# OreSat0_plusZendcard.net
KiCad netlist of a schematic drawn in EAGLE
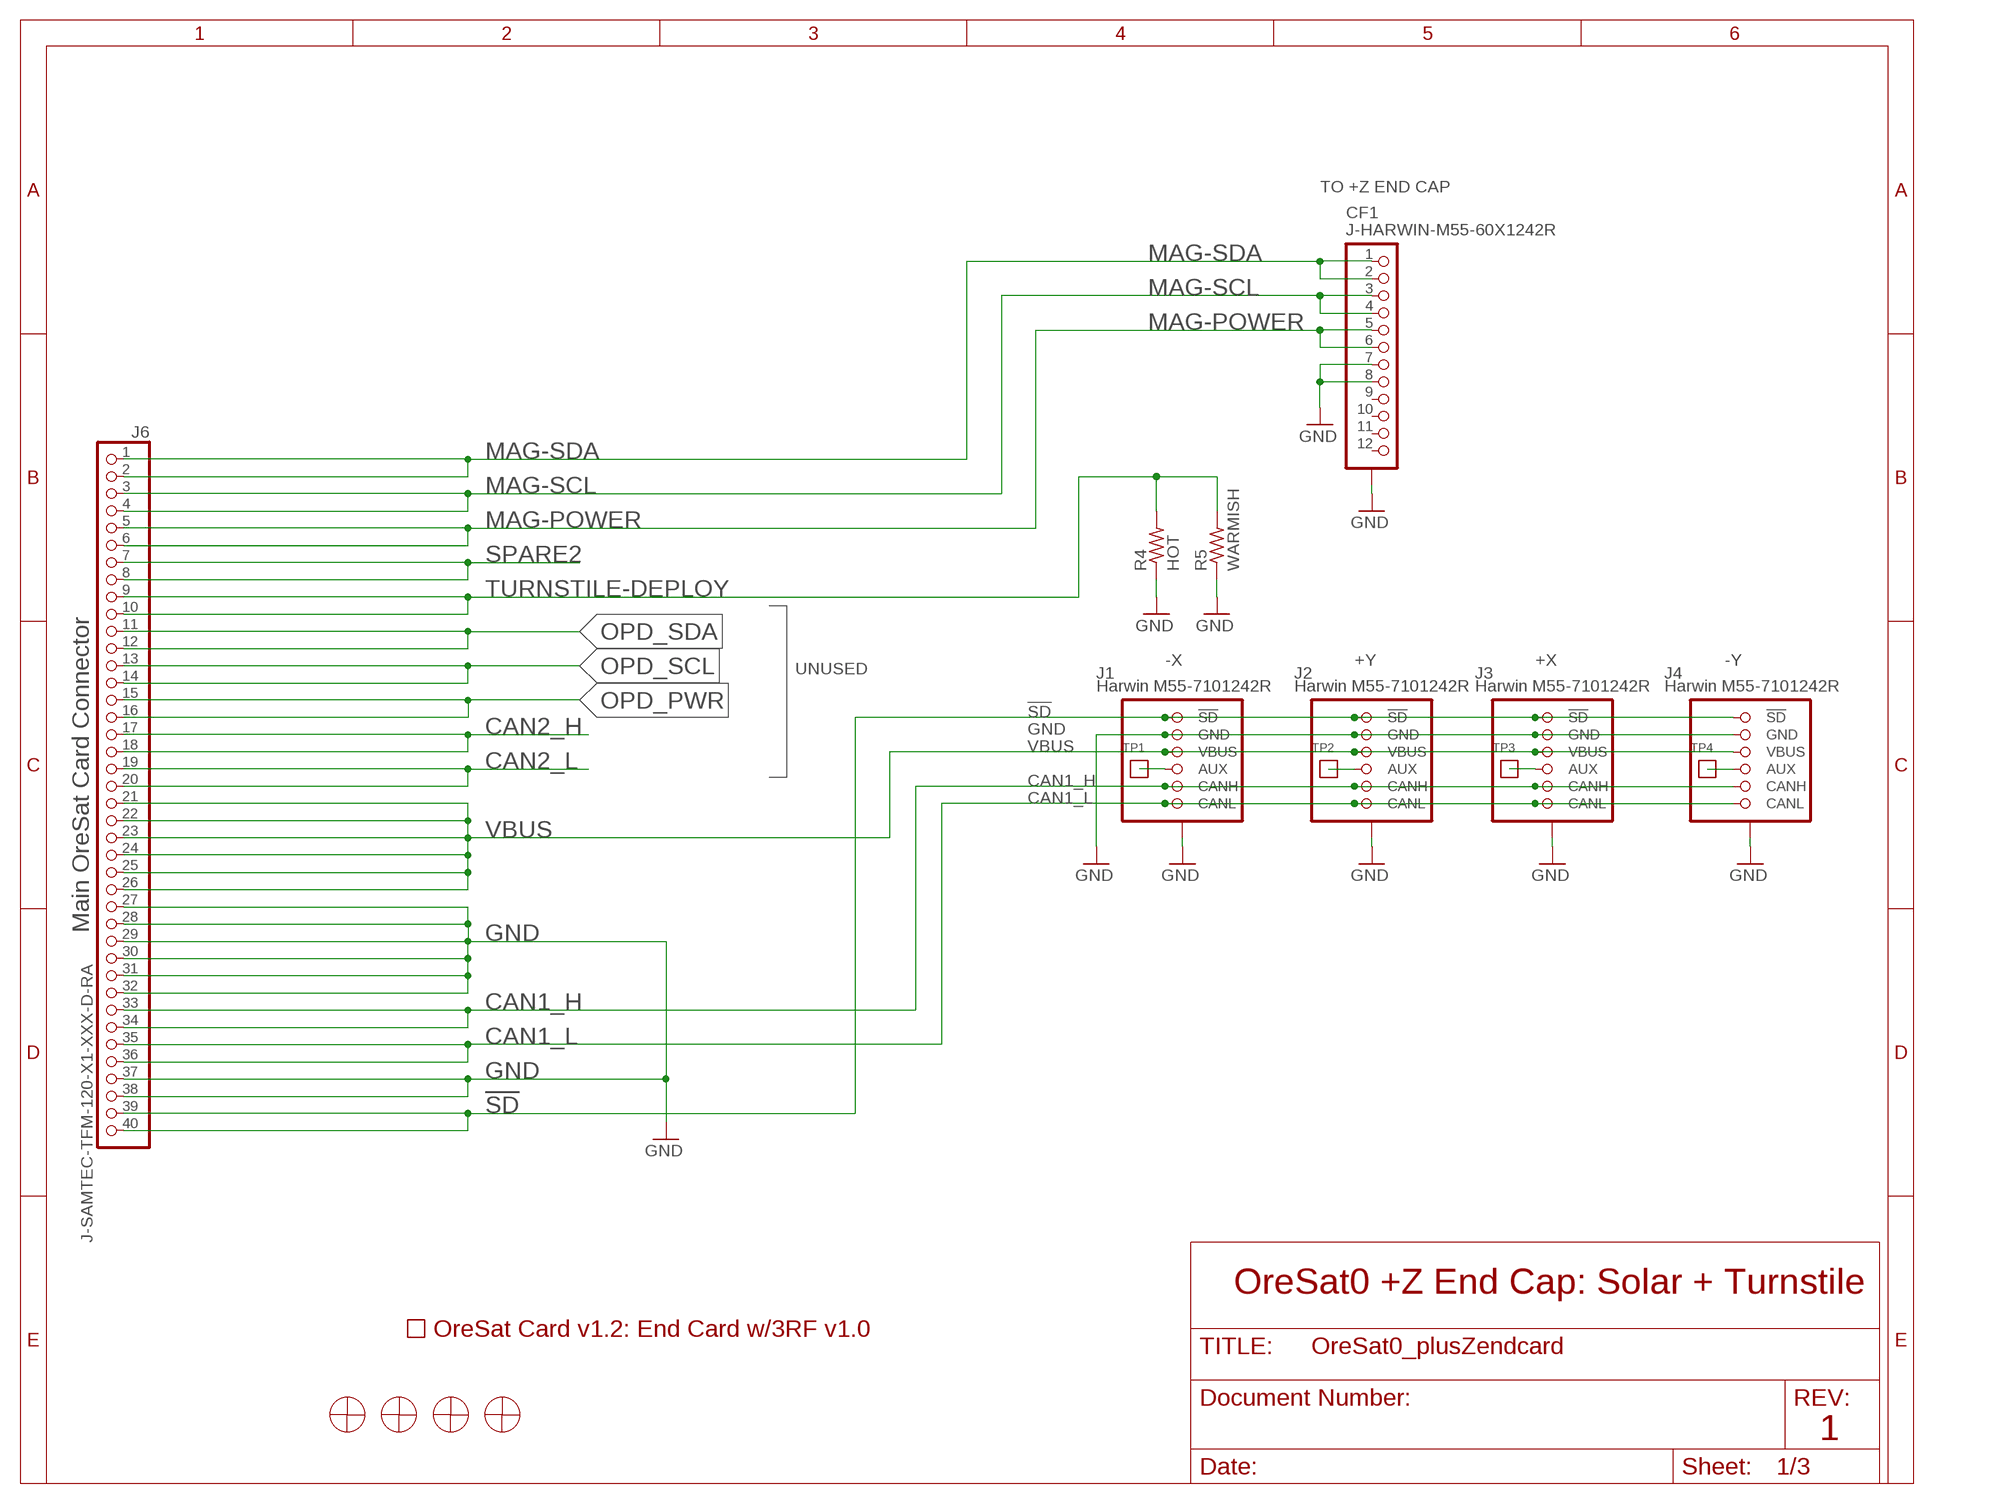
[diagram p0: schematic, sheet 1]
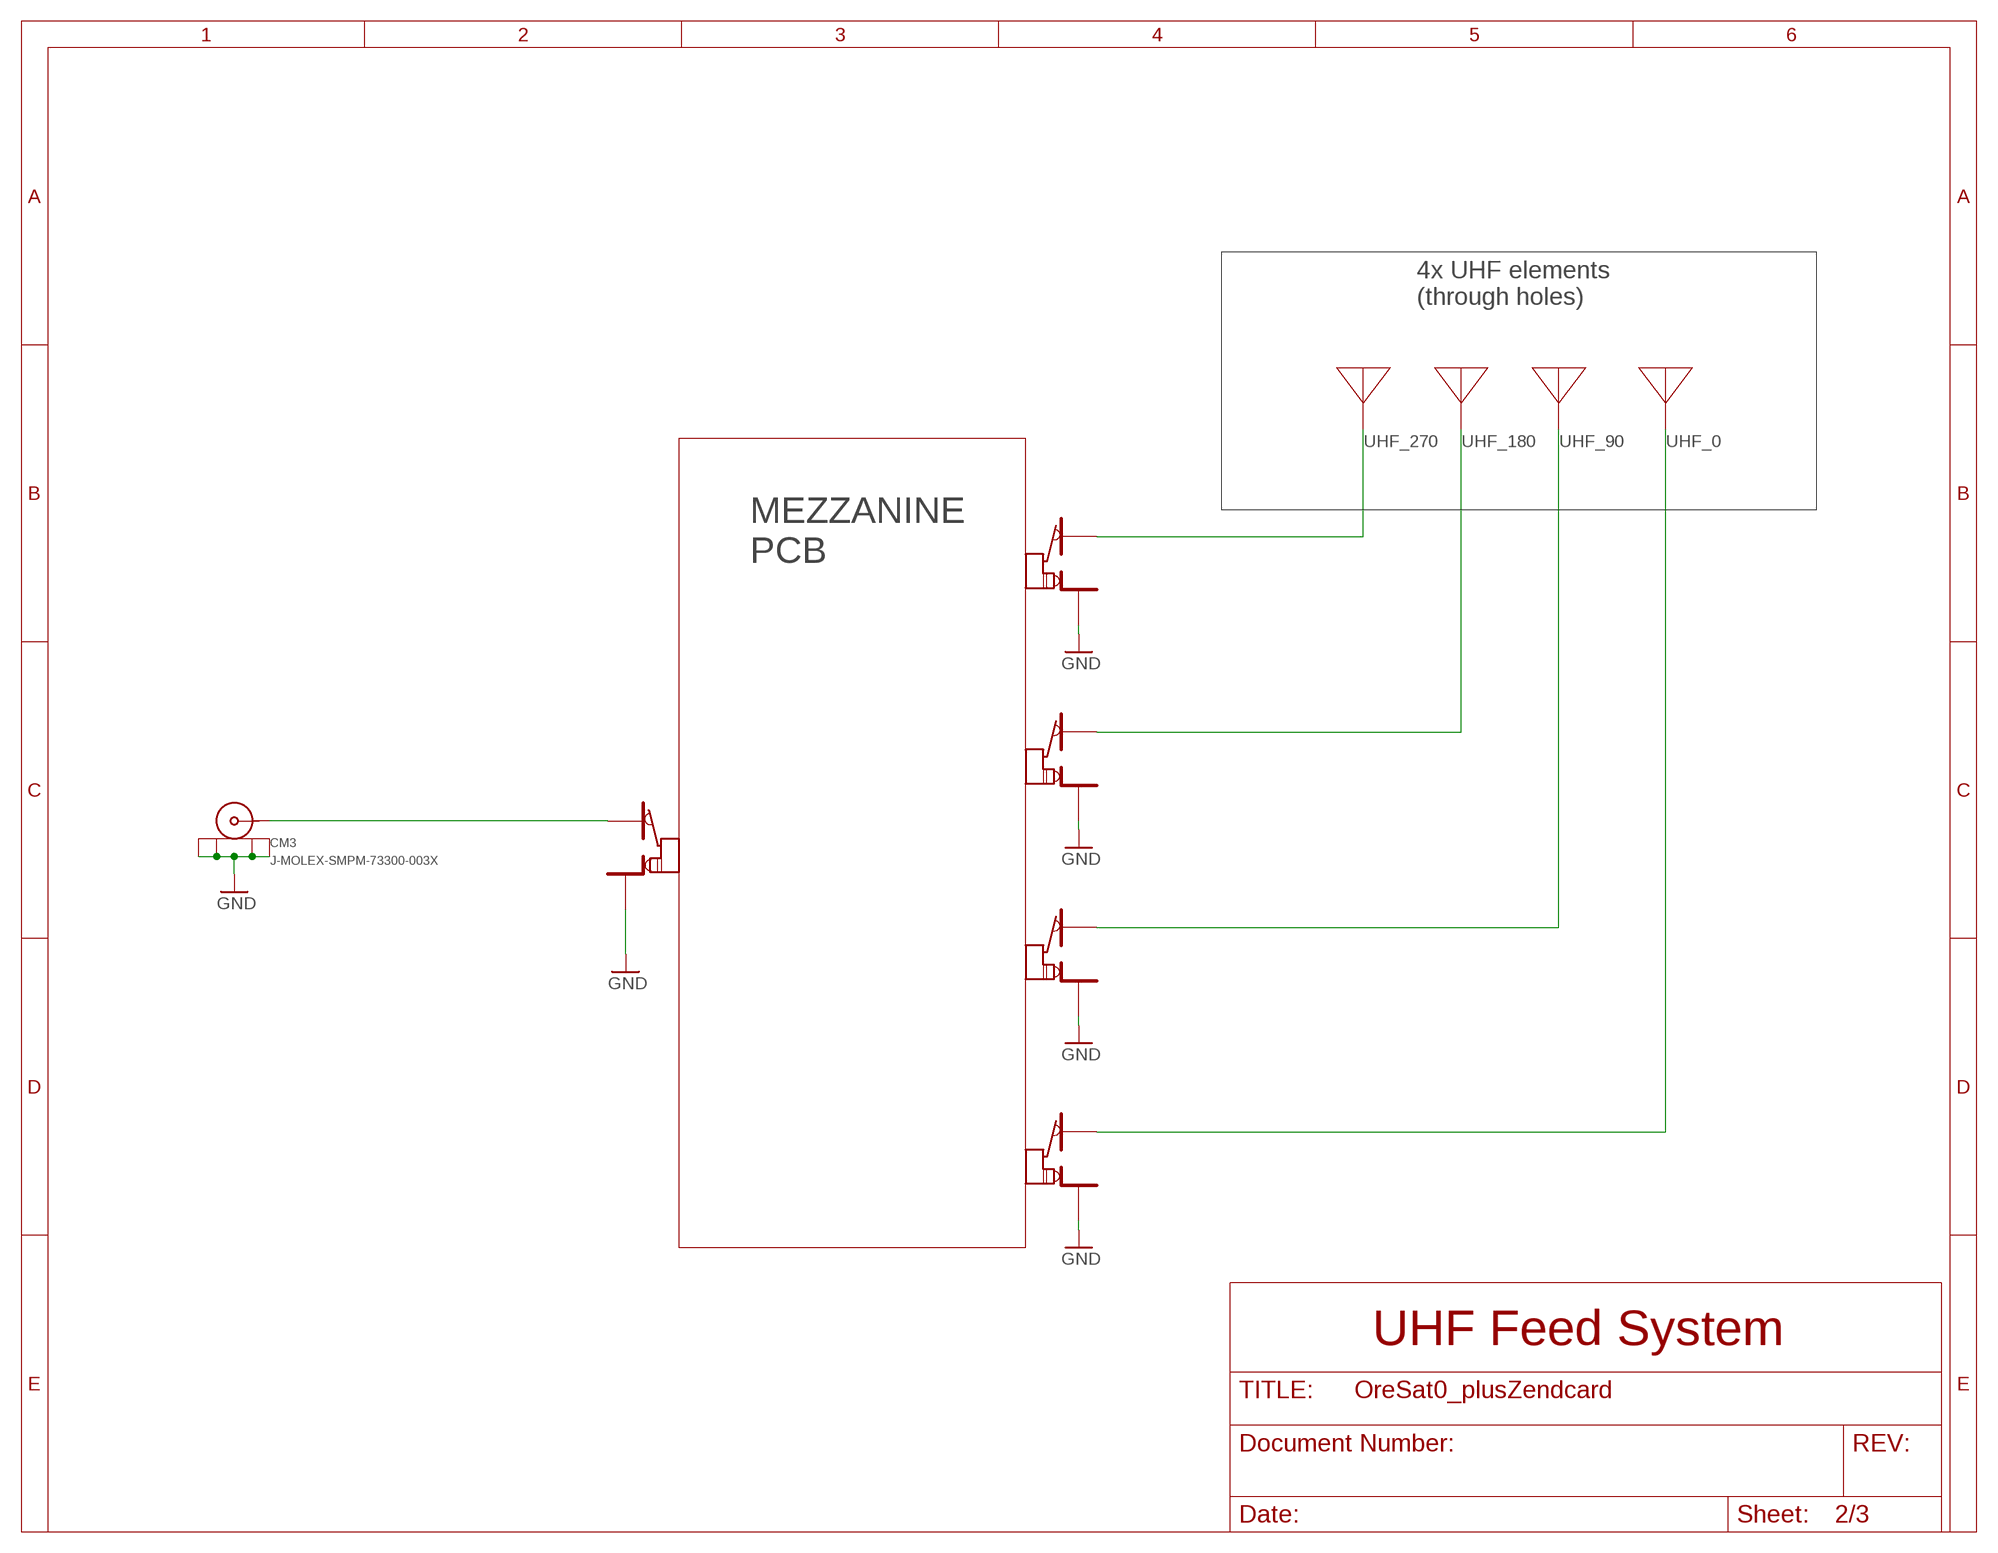
[diagram p1: schematic, sheet 2]
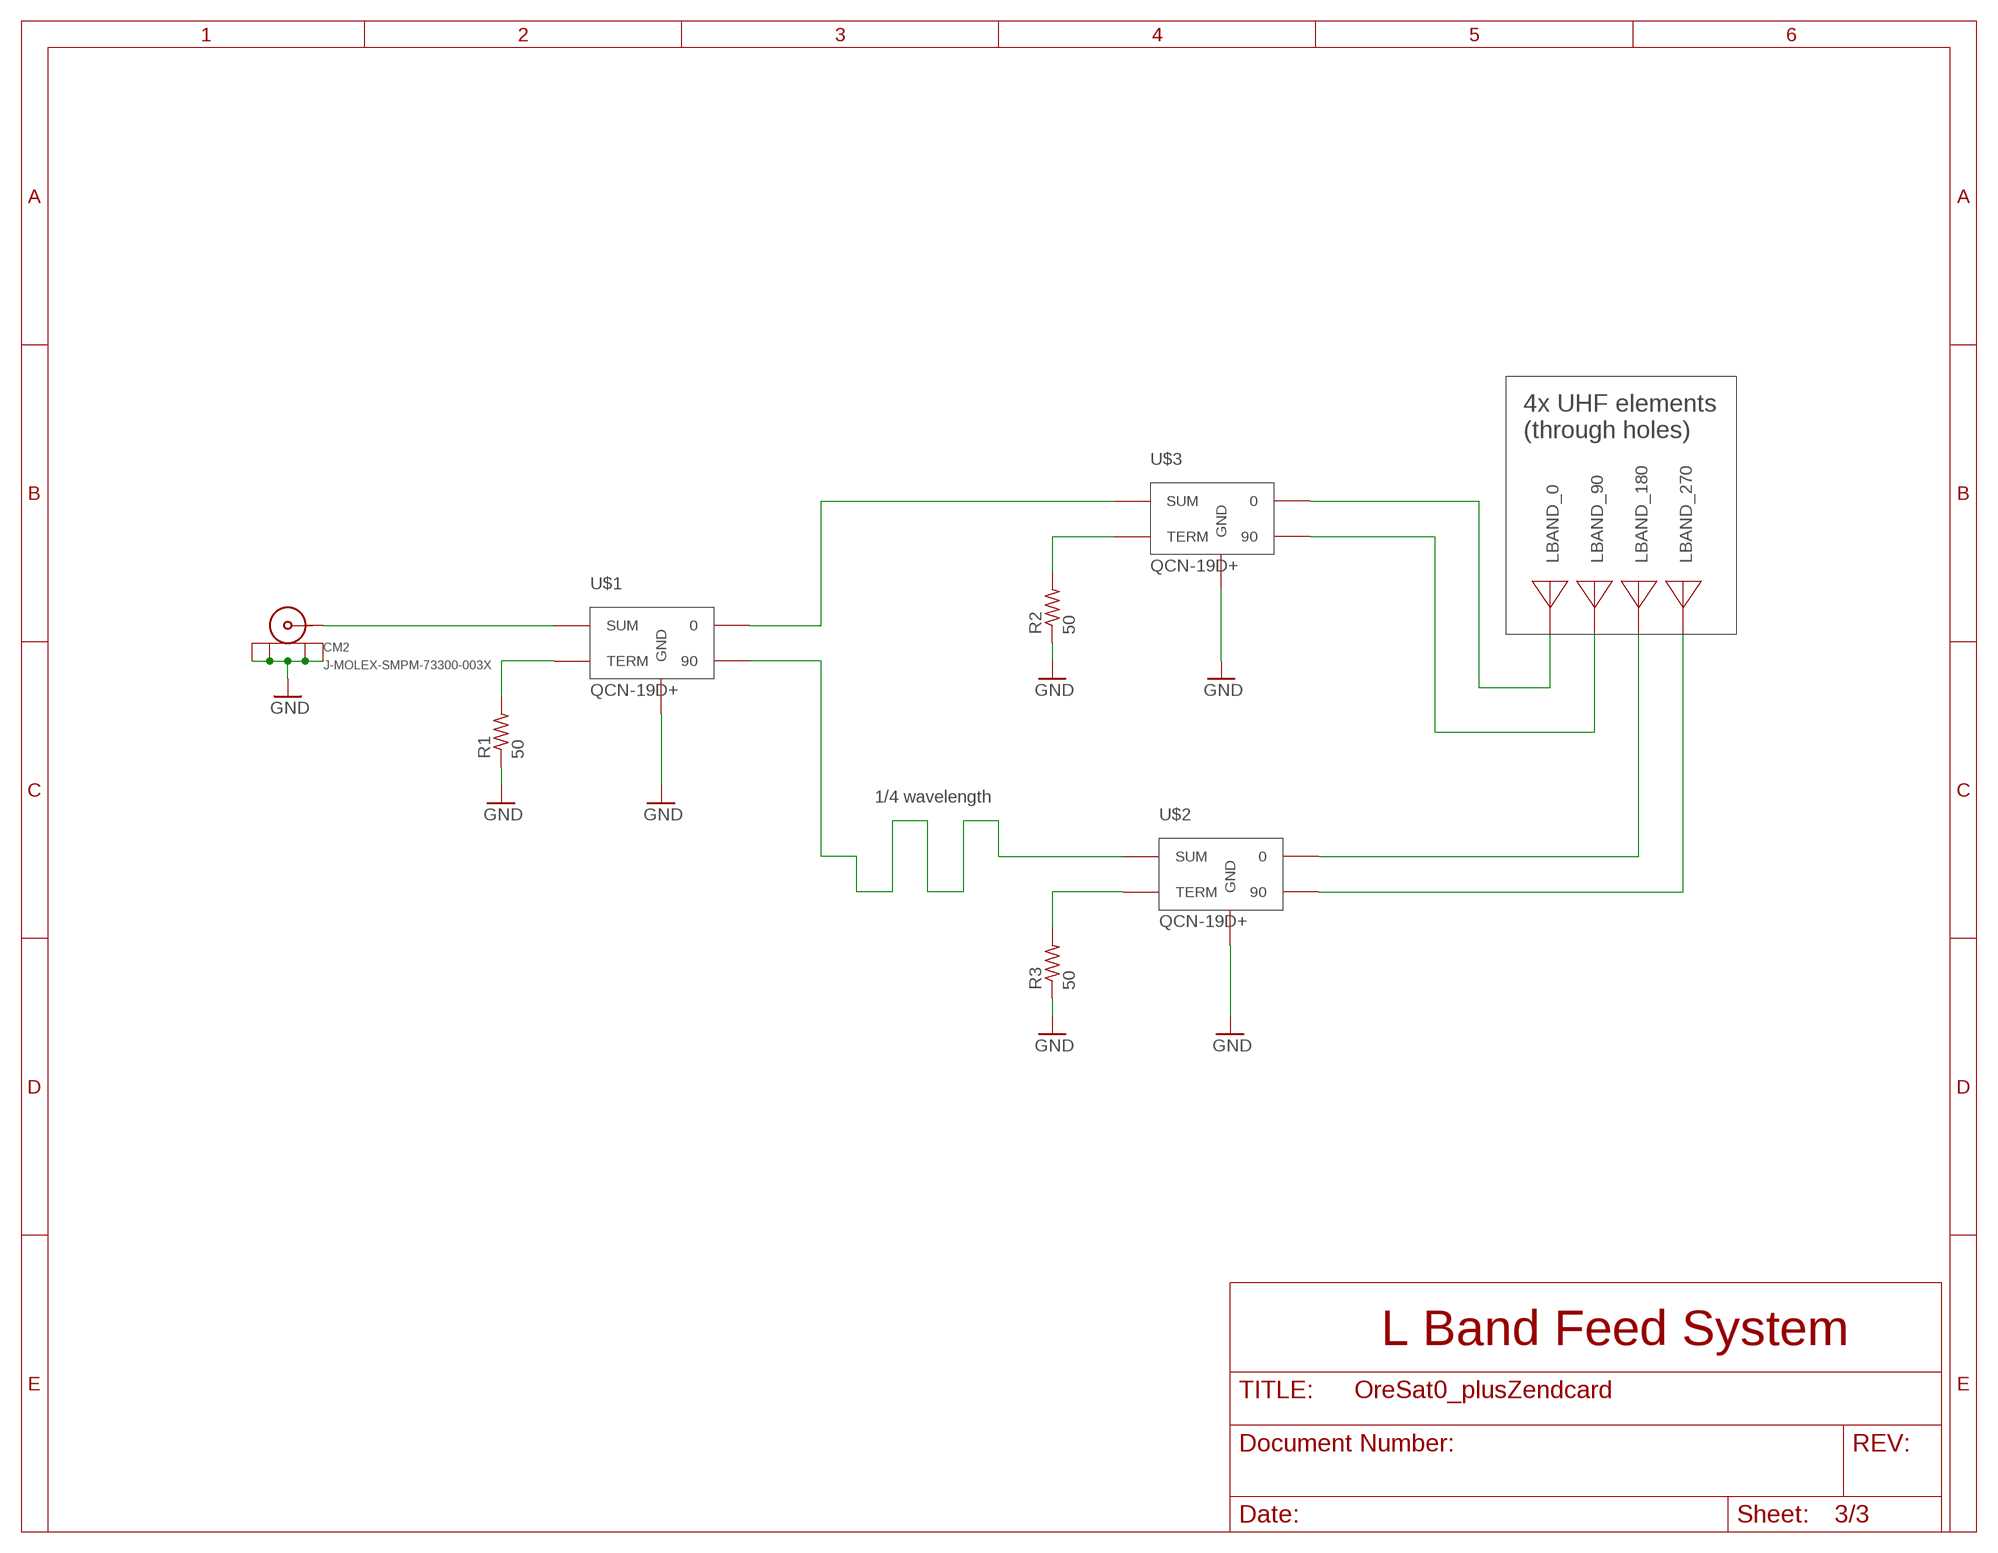
[diagram p2: schematic, sheet 3]

(export (version "E")
  (design (tool "Eeschema 10.0.6"))
  (components
    (comp (ref "CM2")
      (value "J-MOLEX-SMPM-73300-003X")
      (footprint "eagle-import:J-MOLEX-SMPM-73300-003X")
      (fields (field (name "MFG") "MOLEX"))
      (libsource (lib "eagle-import") (part "J-MOLEX-SMPM-73300-003X"))
    )
    (comp (ref "R1")
      (value "50")
      (footprint "eagle-import:.0805-B-NOSILK")
      (libsource (lib "eagle-import") (part "R-US_0805-B-NOSILK"))
    )
    (comp (ref "R2")
      (value "50")
      (footprint "eagle-import:.0805-B-NOSILK")
      (libsource (lib "eagle-import") (part "R-US_0805-B-NOSILK"))
    )
    (comp (ref "R3")
      (value "50")
      (footprint "eagle-import:.0805-B-NOSILK")
      (libsource (lib "eagle-import") (part "R-US_0805-B-NOSILK"))
    )
    (comp (ref "U$1")
      (value "QCN-19D+")
      (footprint "eagle-import:QVN-19D+")
      (libsource (lib "eagle-import") (part "QCN-19D+"))
    )
    (comp (ref "U$2")
      (value "QCN-19D+")
      (footprint "eagle-import:QVN-19D+")
      (libsource (lib "eagle-import") (part "QCN-19D+"))
    )
    (comp (ref "U$3")
      (value "QCN-19D+")
      (footprint "eagle-import:QVN-19D+")
      (libsource (lib "eagle-import") (part "QCN-19D+"))
    )
    (comp (ref "CM3")
      (value "J-MOLEX-SMPM-73300-003X")
      (footprint "eagle-import:J-MOLEX-SMPM-73300-003X")
      (fields (field (name "MFG") "MOLEX"))
      (libsource (lib "eagle-import") (part "J-MOLEX-SMPM-73300-003X"))
    )
    (comp (ref "U$4")
      (value "R107064070_CONTACT")
      (footprint "eagle-import:R107064070_CONTACT")
      (libsource (lib "eagle-import") (part "R107064070_CONTACT"))
    )
    (comp (ref "U$5")
      (value "R107064070_CONTACT")
      (footprint "eagle-import:R107064070_CONTACT")
      (libsource (lib "eagle-import") (part "R107064070_CONTACT"))
    )
    (comp (ref "U$6")
      (value "R107064070_CONTACT")
      (footprint "eagle-import:R107064070_CONTACT")
      (libsource (lib "eagle-import") (part "R107064070_CONTACT"))
    )
    (comp (ref "U$7")
      (value "R107064070_CONTACT")
      (footprint "eagle-import:R107064070_CONTACT")
      (libsource (lib "eagle-import") (part "R107064070_CONTACT"))
    )
    (comp (ref "U$8")
      (value "R107064070_CONTACT")
      (footprint "eagle-import:R107064070_CONTACT")
      (libsource (lib "eagle-import") (part "R107064070_CONTACT"))
    )
    (comp (ref "CF1")
      (value "J-HARWIN-M55-60X1242R")
      (footprint "eagle-import:HARWIN-M55-60X1242R")
      (fields (field (name "MFG") "Harwin"))
      (libsource (lib "eagle-import") (part "J-HARWIN-M55-60X1242R"))
    )
    (comp (ref "J1")
      (value "Harwin M55-7101242R")
      (footprint "eagle-import:M55-7101242R")
      (fields (field (name "MFG") "Harwin Inc."))
      (libsource (lib "eagle-import") (part "SOLAR-CARD-CONNECTOR"))
    )
    (comp (ref "J2")
      (value "Harwin M55-7101242R")
      (footprint "eagle-import:M55-7101242R")
      (fields (field (name "MFG") "Harwin Inc."))
      (libsource (lib "eagle-import") (part "SOLAR-CARD-CONNECTOR"))
    )
    (comp (ref "J3")
      (value "Harwin M55-7101242R")
      (footprint "eagle-import:M55-7101242R")
      (fields (field (name "MFG") "Harwin Inc."))
      (libsource (lib "eagle-import") (part "SOLAR-CARD-CONNECTOR"))
    )
    (comp (ref "J4")
      (value "Harwin M55-7101242R")
      (footprint "eagle-import:M55-7101242R")
      (fields (field (name "MFG") "Harwin Inc."))
      (libsource (lib "eagle-import") (part "SOLAR-CARD-CONNECTOR"))
    )
    (comp (ref "J6")
      (value "J-SAMTEC-TFM-120-X1-XXX-D-RA")
      (footprint "eagle-import:J-SAMTEC-TFM-120-X1-XXX-D-RA")
      (fields (field (name "MFR") "Samtec") (field (name "MPN") "TFM-120-01-L-D-RA"))
      (libsource (lib "eagle-import") (part "J-SAMTEC-TFM-120-X1-XXX-D-RA"))
    )
    (comp (ref "PCB1")
      (value "ORESAT-CARD-V1.3-END-CARD-3RF-V1.0")
      (footprint "eagle-import:ORESAT-CARD-V1.3-END-CARD-3RF-V1.0")
      (libsource (lib "eagle-import") (part "ORESAT-CARD-V1.3-END-CARD-3RF-V1.0"))
    )
    (comp (ref "R4")
      (value "HOT")
      (footprint "eagle-import:0309_12")
      (libsource (lib "eagle-import") (part "R-US_0309/12"))
    )
    (comp (ref "R5")
      (value "WARMISH")
      (footprint "eagle-import:0309_12")
      (libsource (lib "eagle-import") (part "R-US_0309/12"))
    )
    (comp (ref "TP1")
      (value "TEST-POINT-LARGE-SQUARE")
      (footprint "eagle-import:1X01")
      (libsource (lib "eagle-import") (part "TEST-POINT-LARGE-SQUARE"))
    )
    (comp (ref "TP2")
      (value "TEST-POINT-LARGE-SQUARE")
      (footprint "eagle-import:1X01")
      (libsource (lib "eagle-import") (part "TEST-POINT-LARGE-SQUARE"))
    )
    (comp (ref "TP3")
      (value "TEST-POINT-LARGE-SQUARE")
      (footprint "eagle-import:1X01")
      (libsource (lib "eagle-import") (part "TEST-POINT-LARGE-SQUARE"))
    )
    (comp (ref "TP4")
      (value "TEST-POINT-LARGE-SQUARE")
      (footprint "eagle-import:1X01")
      (libsource (lib "eagle-import") (part "TEST-POINT-LARGE-SQUARE"))
    )
    (comp (ref "U$9")
      (value "MCMASTER-94100A150")
      (footprint "eagle-import:MCMASTER-94100A150")
      (libsource (lib "eagle-import") (part "MCMASTER-94100A150"))
    )
    (comp (ref "U$10")
      (value "MCMASTER-94100A150")
      (footprint "eagle-import:MCMASTER-94100A150")
      (libsource (lib "eagle-import") (part "MCMASTER-94100A150"))
    )
    (comp (ref "U$11")
      (value "MCMASTER-94100A150")
      (footprint "eagle-import:MCMASTER-94100A150")
      (libsource (lib "eagle-import") (part "MCMASTER-94100A150"))
    )
    (comp (ref "U$12")
      (value "MCMASTER-94100A150")
      (footprint "eagle-import:MCMASTER-94100A150")
      (libsource (lib "eagle-import") (part "MCMASTER-94100A150"))
    )
  )
  (nets
    (net (code "1") (name "CAN1_H") (class "Default")
      (node (ref "J1") (pin "10") (pinfunction "CANH_10") (pintype "passive"))
      (node (ref "J1") (pin "9") (pinfunction "CANH_9") (pintype "passive"))
      (node (ref "J2") (pin "10") (pinfunction "CANH_10") (pintype "passive"))
      (node (ref "J2") (pin "9") (pinfunction "CANH_9") (pintype "passive"))
      (node (ref "J3") (pin "10") (pinfunction "CANH_10") (pintype "passive"))
      (node (ref "J3") (pin "9") (pinfunction "CANH_9") (pintype "passive"))
      (node (ref "J4") (pin "10") (pinfunction "CANH_10") (pintype "passive"))
      (node (ref "J4") (pin "9") (pinfunction "CANH_9") (pintype "passive"))
      (node (ref "J6") (pin "33") (pinfunction "33_33") (pintype "passive"))
      (node (ref "J6") (pin "34") (pinfunction "34_34") (pintype "passive"))
    )
    (net (code "2") (name "CAN1_L") (class "Default")
      (node (ref "J1") (pin "11") (pinfunction "CANL_11") (pintype "passive"))
      (node (ref "J1") (pin "12") (pinfunction "CANL_12") (pintype "passive"))
      (node (ref "J2") (pin "11") (pinfunction "CANL_11") (pintype "passive"))
      (node (ref "J2") (pin "12") (pinfunction "CANL_12") (pintype "passive"))
      (node (ref "J3") (pin "11") (pinfunction "CANL_11") (pintype "passive"))
      (node (ref "J3") (pin "12") (pinfunction "CANL_12") (pintype "passive"))
      (node (ref "J4") (pin "11") (pinfunction "CANL_11") (pintype "passive"))
      (node (ref "J4") (pin "12") (pinfunction "CANL_12") (pintype "passive"))
      (node (ref "J6") (pin "35") (pinfunction "35_35") (pintype "passive"))
      (node (ref "J6") (pin "36") (pinfunction "36_36") (pintype "passive"))
    )
    (net (code "3") (name "CAN2_H") (class "Default")
      (node (ref "J6") (pin "17") (pinfunction "17_17") (pintype "passive"))
      (node (ref "J6") (pin "18") (pinfunction "18_18") (pintype "passive"))
    )
    (net (code "4") (name "CAN2_L") (class "Default")
      (node (ref "J6") (pin "19") (pinfunction "19_19") (pintype "passive"))
      (node (ref "J6") (pin "20") (pinfunction "20_20") (pintype "passive"))
    )
    (net (code "5") (name "GND") (class "Default")
      (node (ref "CF1") (pin "7") (pinfunction "7_7") (pintype "passive"))
      (node (ref "CF1") (pin "8") (pinfunction "8_8") (pintype "passive"))
      (node (ref "CF1") (pin "P$1") (pinfunction "SHIELDS_P$1") (pintype "passive"))
      (node (ref "CF1") (pin "P$2") (pinfunction "SHIELDS_P$2") (pintype "passive"))
      (node (ref "CF1") (pin "P$3") (pinfunction "SHIELDS_P$3") (pintype "passive"))
      (node (ref "CF1") (pin "P$4") (pinfunction "SHIELDS_P$4") (pintype "passive"))
      (node (ref "CM2") (pin "P$1") (pinfunction "SHIELD3_P$1") (pintype "passive"))
      (node (ref "CM2") (pin "P$2") (pinfunction "SHIELD2_P$2") (pintype "passive"))
      (node (ref "CM2") (pin "P$3") (pinfunction "SHIELD1_P$3") (pintype "passive"))
      (node (ref "CM2") (pin "P$4") (pinfunction "SHIELD_P$4") (pintype "passive"))
      (node (ref "CM3") (pin "P$1") (pinfunction "SHIELD3_P$1") (pintype "passive"))
      (node (ref "CM3") (pin "P$2") (pinfunction "SHIELD2_P$2") (pintype "passive"))
      (node (ref "CM3") (pin "P$3") (pinfunction "SHIELD1_P$3") (pintype "passive"))
      (node (ref "CM3") (pin "P$4") (pinfunction "SHIELD_P$4") (pintype "passive"))
      (node (ref "J1") (pin "3") (pinfunction "GND_3") (pintype "passive"))
      (node (ref "J1") (pin "4") (pinfunction "GND_4") (pintype "passive"))
      (node (ref "J1") (pin "P$1") (pinfunction "SHIELD_P$1") (pintype "passive"))
      (node (ref "J1") (pin "P$2") (pinfunction "SHIELD_P$2") (pintype "passive"))
      (node (ref "J1") (pin "P$3") (pinfunction "SHIELD_P$3") (pintype "passive"))
      (node (ref "J1") (pin "P$4") (pinfunction "SHIELD_P$4") (pintype "passive"))
      (node (ref "J2") (pin "3") (pinfunction "GND_3") (pintype "passive"))
      (node (ref "J2") (pin "4") (pinfunction "GND_4") (pintype "passive"))
      (node (ref "J2") (pin "P$1") (pinfunction "SHIELD_P$1") (pintype "passive"))
      (node (ref "J2") (pin "P$2") (pinfunction "SHIELD_P$2") (pintype "passive"))
      (node (ref "J2") (pin "P$3") (pinfunction "SHIELD_P$3") (pintype "passive"))
      (node (ref "J2") (pin "P$4") (pinfunction "SHIELD_P$4") (pintype "passive"))
      (node (ref "J3") (pin "3") (pinfunction "GND_3") (pintype "passive"))
      (node (ref "J3") (pin "4") (pinfunction "GND_4") (pintype "passive"))
      (node (ref "J3") (pin "P$1") (pinfunction "SHIELD_P$1") (pintype "passive"))
      (node (ref "J3") (pin "P$2") (pinfunction "SHIELD_P$2") (pintype "passive"))
      (node (ref "J3") (pin "P$3") (pinfunction "SHIELD_P$3") (pintype "passive"))
      (node (ref "J3") (pin "P$4") (pinfunction "SHIELD_P$4") (pintype "passive"))
      (node (ref "J4") (pin "3") (pinfunction "GND_3") (pintype "passive"))
      (node (ref "J4") (pin "4") (pinfunction "GND_4") (pintype "passive"))
      (node (ref "J4") (pin "P$1") (pinfunction "SHIELD_P$1") (pintype "passive"))
      (node (ref "J4") (pin "P$2") (pinfunction "SHIELD_P$2") (pintype "passive"))
      (node (ref "J4") (pin "P$3") (pinfunction "SHIELD_P$3") (pintype "passive"))
      (node (ref "J4") (pin "P$4") (pinfunction "SHIELD_P$4") (pintype "passive"))
      (node (ref "J6") (pin "27") (pinfunction "27_27") (pintype "passive"))
      (node (ref "J6") (pin "28") (pinfunction "28_28") (pintype "passive"))
      (node (ref "J6") (pin "29") (pinfunction "29_29") (pintype "passive"))
      (node (ref "J6") (pin "30") (pinfunction "30_30") (pintype "passive"))
      (node (ref "J6") (pin "31") (pinfunction "31_31") (pintype "passive"))
      (node (ref "J6") (pin "32") (pinfunction "32_32") (pintype "passive"))
      (node (ref "J6") (pin "37") (pinfunction "37_37") (pintype "passive"))
      (node (ref "J6") (pin "38") (pinfunction "38_38") (pintype "passive"))
      (node (ref "R1") (pin "1") (pinfunction "1_1") (pintype "passive"))
      (node (ref "R2") (pin "1") (pinfunction "1_1") (pintype "passive"))
      (node (ref "R3") (pin "1") (pinfunction "1_1") (pintype "passive"))
      (node (ref "R4") (pin "1") (pinfunction "1_1") (pintype "passive"))
      (node (ref "R5") (pin "1") (pinfunction "1_1") (pintype "passive"))
      (node (ref "U$1") (pin "P$2") (pinfunction "GND_P$2") (pintype "bidirectional"))
      (node (ref "U$1") (pin "P$5") (pinfunction "GND_P$5") (pintype "bidirectional"))
      (node (ref "U$2") (pin "P$2") (pinfunction "GND_P$2") (pintype "bidirectional"))
      (node (ref "U$2") (pin "P$5") (pinfunction "GND_P$5") (pintype "bidirectional"))
      (node (ref "U$3") (pin "P$2") (pinfunction "GND_P$2") (pintype "bidirectional"))
      (node (ref "U$3") (pin "P$5") (pinfunction "GND_P$5") (pintype "bidirectional"))
      (node (ref "U$4") (pin "P$2") (pinfunction "P$2_P$2") (pintype "bidirectional"))
      (node (ref "U$4") (pin "P$3") (pinfunction "P$2_P$3") (pintype "bidirectional"))
      (node (ref "U$5") (pin "P$2") (pinfunction "P$2_P$2") (pintype "bidirectional"))
      (node (ref "U$5") (pin "P$3") (pinfunction "P$2_P$3") (pintype "bidirectional"))
      (node (ref "U$6") (pin "P$2") (pinfunction "P$2_P$2") (pintype "bidirectional"))
      (node (ref "U$6") (pin "P$3") (pinfunction "P$2_P$3") (pintype "bidirectional"))
      (node (ref "U$7") (pin "P$2") (pinfunction "P$2_P$2") (pintype "bidirectional"))
      (node (ref "U$7") (pin "P$3") (pinfunction "P$2_P$3") (pintype "bidirectional"))
      (node (ref "U$8") (pin "P$2") (pinfunction "P$2_P$2") (pintype "bidirectional"))
      (node (ref "U$8") (pin "P$3") (pinfunction "P$2_P$3") (pintype "bidirectional"))
    )
    (net (code "6") (name "LBAND_0") (class "Default")
      (node (ref "U$3") (pin "P$4") (pinfunction "0_P$4") (pintype "bidirectional"))
    )
    (net (code "7") (name "LBAND_90") (class "Default")
      (node (ref "U$3") (pin "P$6") (pinfunction "90_P$6") (pintype "bidirectional"))
    )
    (net (code "8") (name "LBAND_180") (class "Default")
      (node (ref "U$2") (pin "P$4") (pinfunction "0_P$4") (pintype "bidirectional"))
    )
    (net (code "9") (name "LBAND_270") (class "Default")
      (node (ref "U$2") (pin "P$6") (pinfunction "90_P$6") (pintype "bidirectional"))
    )
    (net (code "10") (name "MAG-POWER") (class "Default")
      (node (ref "CF1") (pin "5") (pinfunction "5_5") (pintype "passive"))
      (node (ref "CF1") (pin "6") (pinfunction "6_6") (pintype "passive"))
      (node (ref "J6") (pin "5") (pinfunction "5_5") (pintype "passive"))
      (node (ref "J6") (pin "6") (pinfunction "6_6") (pintype "passive"))
    )
    (net (code "11") (name "MAG-SCL") (class "Default")
      (node (ref "CF1") (pin "3") (pinfunction "3_3") (pintype "passive"))
      (node (ref "CF1") (pin "4") (pinfunction "4_4") (pintype "passive"))
      (node (ref "J6") (pin "3") (pinfunction "3_3") (pintype "passive"))
      (node (ref "J6") (pin "4") (pinfunction "4_4") (pintype "passive"))
    )
    (net (code "12") (name "MAG-SDA") (class "Default")
      (node (ref "CF1") (pin "1") (pinfunction "1_1") (pintype "passive"))
      (node (ref "CF1") (pin "2") (pinfunction "2_2") (pintype "passive"))
      (node (ref "J6") (pin "1") (pinfunction "1_1") (pintype "passive"))
      (node (ref "J6") (pin "2") (pinfunction "2_2") (pintype "passive"))
    )
    (net (code "13") (name "Net-(CM2-CENTER)") (class "Default")
      (node (ref "CM2") (pin "RF") (pinfunction "CENTER_RF") (pintype "passive"))
      (node (ref "U$1") (pin "P$1") (pinfunction "SUM_P$1") (pintype "bidirectional"))
    )
    (net (code "14") (name "Net-(CM3-CENTER)") (class "Default")
      (node (ref "CM3") (pin "RF") (pinfunction "CENTER_RF") (pintype "passive"))
      (node (ref "U$4") (pin "P$1") (pinfunction "P$1_P$1") (pintype "bidirectional"))
    )
    (net (code "15") (name "Net-(J1-AUX-Pad7)") (class "Default")
      (node (ref "J1") (pin "7") (pinfunction "AUX_7") (pintype "passive"))
      (node (ref "J1") (pin "8") (pinfunction "AUX_8") (pintype "passive"))
      (node (ref "TP1") (pin "1") (pinfunction "1_1") (pintype "passive"))
    )
    (net (code "16") (name "Net-(J2-AUX-Pad7)") (class "Default")
      (node (ref "J2") (pin "7") (pinfunction "AUX_7") (pintype "passive"))
      (node (ref "J2") (pin "8") (pinfunction "AUX_8") (pintype "passive"))
      (node (ref "TP2") (pin "1") (pinfunction "1_1") (pintype "passive"))
    )
    (net (code "17") (name "Net-(J3-AUX-Pad7)") (class "Default")
      (node (ref "J3") (pin "7") (pinfunction "AUX_7") (pintype "passive"))
      (node (ref "J3") (pin "8") (pinfunction "AUX_8") (pintype "passive"))
      (node (ref "TP3") (pin "1") (pinfunction "1_1") (pintype "passive"))
    )
    (net (code "18") (name "Net-(J4-AUX-Pad7)") (class "Default")
      (node (ref "J4") (pin "7") (pinfunction "AUX_7") (pintype "passive"))
      (node (ref "J4") (pin "8") (pinfunction "AUX_8") (pintype "passive"))
      (node (ref "TP4") (pin "1") (pinfunction "1_1") (pintype "passive"))
    )
    (net (code "19") (name "Net-(U$1-0)") (class "Default")
      (node (ref "U$1") (pin "P$4") (pinfunction "0_P$4") (pintype "bidirectional"))
      (node (ref "U$3") (pin "P$1") (pinfunction "SUM_P$1") (pintype "bidirectional"))
    )
    (net (code "20") (name "Net-(U$1-90)") (class "Default")
      (node (ref "U$1") (pin "P$6") (pinfunction "90_P$6") (pintype "bidirectional"))
      (node (ref "U$2") (pin "P$1") (pinfunction "SUM_P$1") (pintype "bidirectional"))
    )
    (net (code "21") (name "Net-(U$1-TERM)") (class "Default")
      (node (ref "R1") (pin "2") (pinfunction "2_2") (pintype "passive"))
      (node (ref "U$1") (pin "P$3") (pinfunction "TERM_P$3") (pintype "bidirectional"))
    )
    (net (code "22") (name "Net-(U$2-TERM)") (class "Default")
      (node (ref "R3") (pin "2") (pinfunction "2_2") (pintype "passive"))
      (node (ref "U$2") (pin "P$3") (pinfunction "TERM_P$3") (pintype "bidirectional"))
    )
    (net (code "23") (name "Net-(U$3-TERM)") (class "Default")
      (node (ref "R2") (pin "2") (pinfunction "2_2") (pintype "passive"))
      (node (ref "U$3") (pin "P$3") (pinfunction "TERM_P$3") (pintype "bidirectional"))
    )
    (net (code "24") (name "OPD_PWR") (class "Default")
      (node (ref "J6") (pin "15") (pinfunction "15_15") (pintype "passive"))
      (node (ref "J6") (pin "16") (pinfunction "16_16") (pintype "passive"))
    )
    (net (code "25") (name "OPD_SCL") (class "Default")
      (node (ref "J6") (pin "13") (pinfunction "13_13") (pintype "passive"))
      (node (ref "J6") (pin "14") (pinfunction "14_14") (pintype "passive"))
    )
    (net (code "26") (name "OPD_SDA") (class "Default")
      (node (ref "J6") (pin "11") (pinfunction "11_11") (pintype "passive"))
      (node (ref "J6") (pin "12") (pinfunction "12_12") (pintype "passive"))
    )
    (net (code "27") (name "SPARE2") (class "Default")
      (node (ref "J6") (pin "7") (pinfunction "7_7") (pintype "passive"))
      (node (ref "J6") (pin "8") (pinfunction "8_8") (pintype "passive"))
    )
    (net (code "28") (name "TURNSTILE-DEPLOY") (class "Default")
      (node (ref "J6") (pin "10") (pinfunction "10_10") (pintype "passive"))
      (node (ref "J6") (pin "9") (pinfunction "9_9") (pintype "passive"))
      (node (ref "R4") (pin "2") (pinfunction "2_2") (pintype "passive"))
      (node (ref "R5") (pin "2") (pinfunction "2_2") (pintype "passive"))
    )
    (net (code "29") (name "UHF_0") (class "Default")
      (node (ref "U$8") (pin "P$1") (pinfunction "P$1_P$1") (pintype "bidirectional"))
    )
    (net (code "30") (name "UHF_90") (class "Default")
      (node (ref "U$7") (pin "P$1") (pinfunction "P$1_P$1") (pintype "bidirectional"))
    )
    (net (code "31") (name "UHF_180") (class "Default")
      (node (ref "U$6") (pin "P$1") (pinfunction "P$1_P$1") (pintype "bidirectional"))
    )
    (net (code "32") (name "UHF_270") (class "Default")
      (node (ref "U$5") (pin "P$1") (pinfunction "P$1_P$1") (pintype "bidirectional"))
    )
    (net (code "33") (name "VBUS") (class "Default")
      (node (ref "J1") (pin "5") (pinfunction "VBUS_5") (pintype "passive"))
      (node (ref "J1") (pin "6") (pinfunction "VBUS_6") (pintype "passive"))
      (node (ref "J2") (pin "5") (pinfunction "VBUS_5") (pintype "passive"))
      (node (ref "J2") (pin "6") (pinfunction "VBUS_6") (pintype "passive"))
      (node (ref "J3") (pin "5") (pinfunction "VBUS_5") (pintype "passive"))
      (node (ref "J3") (pin "6") (pinfunction "VBUS_6") (pintype "passive"))
      (node (ref "J4") (pin "5") (pinfunction "VBUS_5") (pintype "passive"))
      (node (ref "J4") (pin "6") (pinfunction "VBUS_6") (pintype "passive"))
      (node (ref "J6") (pin "21") (pinfunction "21_21") (pintype "passive"))
      (node (ref "J6") (pin "22") (pinfunction "22_22") (pintype "passive"))
      (node (ref "J6") (pin "23") (pinfunction "23_23") (pintype "passive"))
      (node (ref "J6") (pin "24") (pinfunction "24_24") (pintype "passive"))
      (node (ref "J6") (pin "25") (pinfunction "25_25") (pintype "passive"))
      (node (ref "J6") (pin "26") (pinfunction "26_26") (pintype "passive"))
    )
    (net (code "34") (name "unconnected-(CF1-Pad9)") (class "Default")
      (node (ref "CF1") (pin "9") (pinfunction "9_9") (pintype "passive"))
    )
    (net (code "35") (name "unconnected-(CF1-Pad10)") (class "Default")
      (node (ref "CF1") (pin "10") (pinfunction "10_10") (pintype "passive"))
    )
    (net (code "36") (name "unconnected-(CF1-Pad11)") (class "Default")
      (node (ref "CF1") (pin "11") (pinfunction "11_11") (pintype "passive"))
    )
    (net (code "37") (name "unconnected-(CF1-Pad12)") (class "Default")
      (node (ref "CF1") (pin "12") (pinfunction "12_12") (pintype "passive"))
    )
    (net (code "38") (name "~{SD}") (class "Default")
      (node (ref "J1") (pin "1") (pinfunction "~{SD}_1") (pintype "passive"))
      (node (ref "J1") (pin "2") (pinfunction "~{SD}_2") (pintype "passive"))
      (node (ref "J2") (pin "1") (pinfunction "~{SD}_1") (pintype "passive"))
      (node (ref "J2") (pin "2") (pinfunction "~{SD}_2") (pintype "passive"))
      (node (ref "J3") (pin "1") (pinfunction "~{SD}_1") (pintype "passive"))
      (node (ref "J3") (pin "2") (pinfunction "~{SD}_2") (pintype "passive"))
      (node (ref "J4") (pin "1") (pinfunction "~{SD}_1") (pintype "passive"))
      (node (ref "J4") (pin "2") (pinfunction "~{SD}_2") (pintype "passive"))
      (node (ref "J6") (pin "39") (pinfunction "39_39") (pintype "passive"))
      (node (ref "J6") (pin "40") (pinfunction "40_40") (pintype "passive"))
    )
  )
)
